# Driver.net
KiCad netlist of a schematic drawn in EAGLE
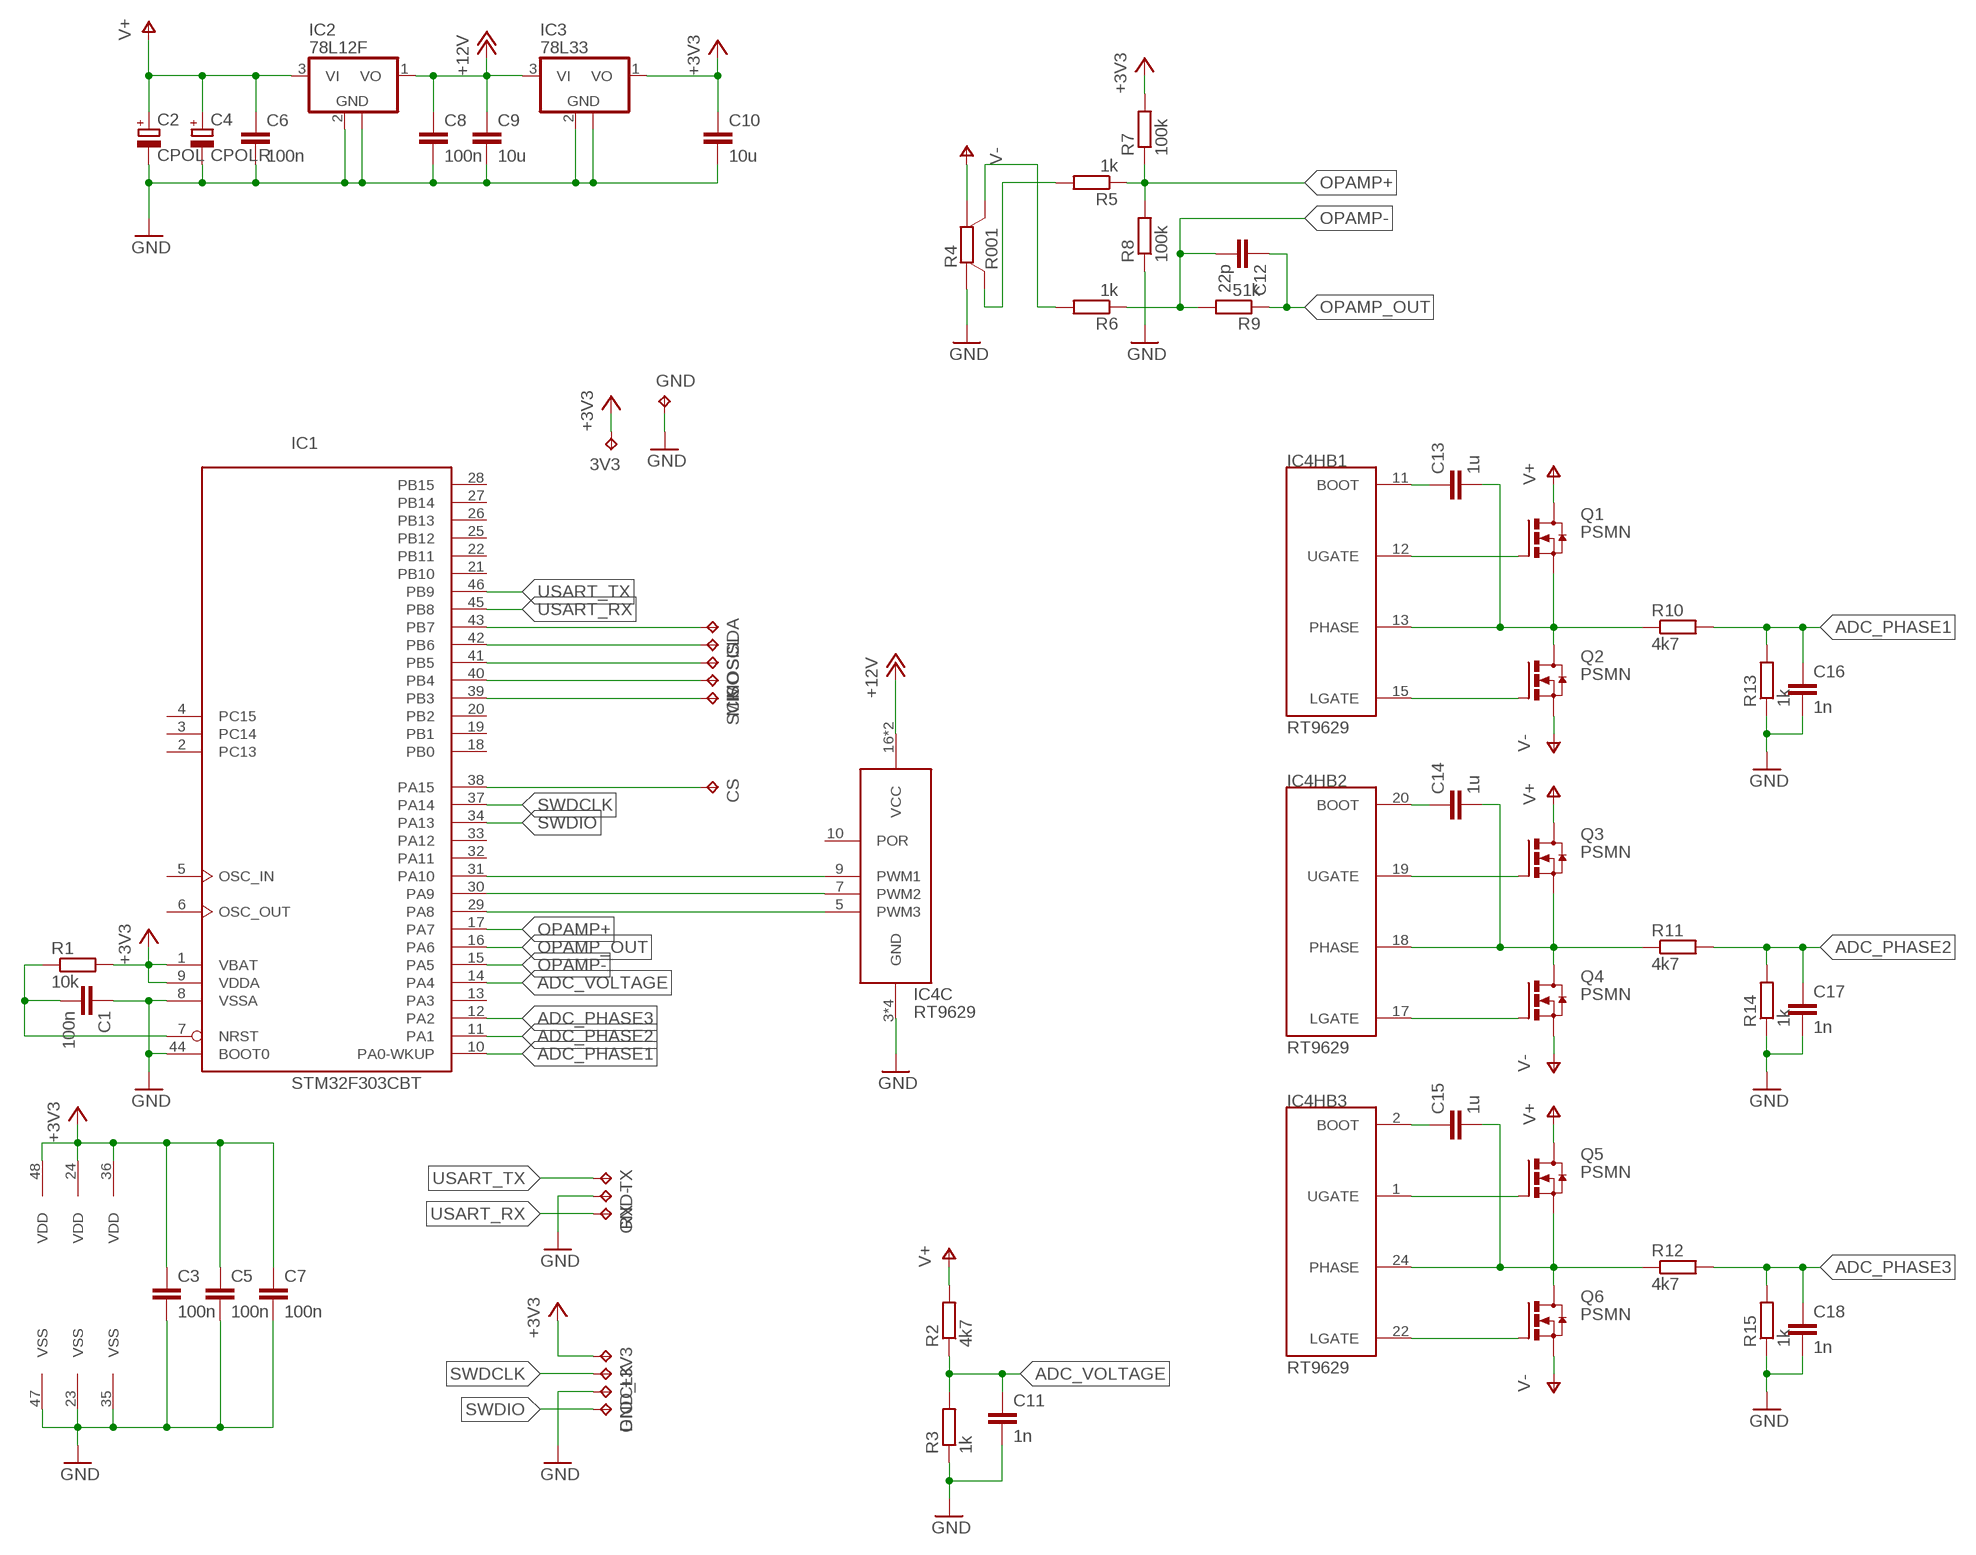
[diagram p0: schematic, sheet 1]

(export (version "E")
  (design (tool "Eeschema 10.0.6"))
  (components
    (comp (ref "+3V3")
      (value "TPTP15R")
      (footprint "eagle-import:TP15R")
      (libsource (lib "eagle-import") (part "TPTP15R"))
    )
    (comp (ref "3V3")
      (value "TPTP10SQ")
      (footprint "eagle-import:TP10SQ")
      (libsource (lib "eagle-import") (part "TPTP10SQ"))
    )
    (comp (ref "C1")
      (value "100n")
      (footprint "eagle-import:C0603K")
      (libsource (lib "eagle-import") (part "C-EUC0603K"))
    )
    (comp (ref "C2")
      (value "CPOL")
      (footprint "eagle-import:SIDEWAYS-5.08")
      (libsource (lib "eagle-import") (part "CPOL"))
    )
    (comp (ref "C3")
      (value "100n")
      (footprint "eagle-import:C0603K")
      (libsource (lib "eagle-import") (part "C-EUC0603K"))
    )
    (comp (ref "C4")
      (value "CPOLR")
      (footprint "eagle-import:SIDEWAYS-5.08R")
      (libsource (lib "eagle-import") (part "CPOLR"))
    )
    (comp (ref "C5")
      (value "100n")
      (footprint "eagle-import:C0603K")
      (libsource (lib "eagle-import") (part "C-EUC0603K"))
    )
    (comp (ref "C6")
      (value "100n")
      (footprint "eagle-import:C0603K")
      (libsource (lib "eagle-import") (part "C-EUC0603K"))
    )
    (comp (ref "C7")
      (value "100n")
      (footprint "eagle-import:C0603K")
      (libsource (lib "eagle-import") (part "C-EUC0603K"))
    )
    (comp (ref "C8")
      (value "100n")
      (footprint "eagle-import:C0603K")
      (libsource (lib "eagle-import") (part "C-EUC0603K"))
    )
    (comp (ref "C9")
      (value "10u")
      (footprint "eagle-import:C1206K")
      (libsource (lib "eagle-import") (part "C-EUC1206K"))
    )
    (comp (ref "C10")
      (value "10u")
      (footprint "eagle-import:C1206K")
      (libsource (lib "eagle-import") (part "C-EUC1206K"))
    )
    (comp (ref "C11")
      (value "1n")
      (footprint "eagle-import:C0603K")
      (libsource (lib "eagle-import") (part "C-EUC0603K"))
    )
    (comp (ref "C12")
      (value "22p")
      (footprint "eagle-import:C0603K")
      (libsource (lib "eagle-import") (part "C-EUC0603K"))
    )
    (comp (ref "C13")
      (value "1u")
      (footprint "eagle-import:C0603K")
      (libsource (lib "eagle-import") (part "C-EUC0603K"))
    )
    (comp (ref "C14")
      (value "1u")
      (footprint "eagle-import:C0603K")
      (libsource (lib "eagle-import") (part "C-EUC0603K"))
    )
    (comp (ref "C15")
      (value "1u")
      (footprint "eagle-import:C0603K")
      (libsource (lib "eagle-import") (part "C-EUC0603K"))
    )
    (comp (ref "C16")
      (value "1n")
      (footprint "eagle-import:C0603K")
      (libsource (lib "eagle-import") (part "C-EUC0603K"))
    )
    (comp (ref "C17")
      (value "1n")
      (footprint "eagle-import:C0603K")
      (libsource (lib "eagle-import") (part "C-EUC0603K"))
    )
    (comp (ref "C18")
      (value "1n")
      (footprint "eagle-import:C0603K")
      (libsource (lib "eagle-import") (part "C-EUC0603K"))
    )
    (comp (ref "CLK")
      (value "TPTP15R")
      (footprint "eagle-import:TP15R")
      (libsource (lib "eagle-import") (part "TPTP15R"))
    )
    (comp (ref "CS")
      (value "TPTP10SQ")
      (footprint "eagle-import:TP10SQ")
      (libsource (lib "eagle-import") (part "TPTP10SQ"))
    )
    (comp (ref "DIO")
      (value "TPTP15R")
      (footprint "eagle-import:TP15R")
      (libsource (lib "eagle-import") (part "TPTP15R"))
    )
    (comp (ref "GND")
      (value "TPTP10SQ")
      (footprint "eagle-import:TP10SQ")
      (libsource (lib "eagle-import") (part "TPTP10SQ"))
    )
    (comp (ref "GND-")
      (value "TPTP15SQ")
      (footprint "eagle-import:TP15SQ")
      (libsource (lib "eagle-import") (part "TPTP15SQ"))
    )
    (comp (ref "GND_")
      (value "TPTP15SQ")
      (footprint "eagle-import:TP15SQ")
      (libsource (lib "eagle-import") (part "TPTP15SQ"))
    )
    (comp (ref "IC1")
      (value "STM32F303CBT")
      (footprint "eagle-import:LQFP48")
      (libsource (lib "eagle-import") (part "STM32F303CTB"))
    )
    (comp (ref "IC2")
      (value "78L12F")
      (footprint "eagle-import:SOT89")
      (libsource (lib "eagle-import") (part "78LF12"))
    )
    (comp (ref "IC3")
      (value "78L33")
      (footprint "eagle-import:SOT89")
      (libsource (lib "eagle-import") (part "78LF12"))
    )
    (comp (ref "IC4")
      (value "RT9629")
      (footprint "eagle-import:WQFN24")
      (libsource (lib "eagle-import") (part "RT9629"))
    )
    (comp (ref "MISO")
      (value "TPTP10SQ")
      (footprint "eagle-import:TP10SQ")
      (libsource (lib "eagle-import") (part "TPTP10SQ"))
    )
    (comp (ref "MOSI")
      (value "TPTP10SQ")
      (footprint "eagle-import:TP10SQ")
      (libsource (lib "eagle-import") (part "TPTP10SQ"))
    )
    (comp (ref "Q1")
      (value "PSMN")
      (footprint "eagle-import:SOT669")
      (libsource (lib "eagle-import") (part "PSMN"))
    )
    (comp (ref "Q2")
      (value "PSMN")
      (footprint "eagle-import:SOT669")
      (libsource (lib "eagle-import") (part "PSMN"))
    )
    (comp (ref "Q3")
      (value "PSMN")
      (footprint "eagle-import:SOT669")
      (libsource (lib "eagle-import") (part "PSMN"))
    )
    (comp (ref "Q4")
      (value "PSMN")
      (footprint "eagle-import:SOT669")
      (libsource (lib "eagle-import") (part "PSMN"))
    )
    (comp (ref "Q5")
      (value "PSMN")
      (footprint "eagle-import:SOT669")
      (libsource (lib "eagle-import") (part "PSMN"))
    )
    (comp (ref "Q6")
      (value "PSMN")
      (footprint "eagle-import:SOT669")
      (libsource (lib "eagle-import") (part "PSMN"))
    )
    (comp (ref "R1")
      (value "10k")
      (footprint "eagle-import:R0603")
      (libsource (lib "eagle-import") (part "R-EU_R0603"))
    )
    (comp (ref "R2")
      (value "4k7")
      (footprint "eagle-import:R0603")
      (libsource (lib "eagle-import") (part "R-EU_R0603"))
    )
    (comp (ref "R3")
      (value "1k")
      (footprint "eagle-import:R0603")
      (libsource (lib "eagle-import") (part "R-EU_R0603"))
    )
    (comp (ref "R4")
      (value "R001")
      (footprint "eagle-import:WSK1216")
      (libsource (lib "eagle-import") (part "VISHAY_WSK1216"))
    )
    (comp (ref "R5")
      (value "1k")
      (footprint "eagle-import:R0603")
      (libsource (lib "eagle-import") (part "R-EU_R0603"))
    )
    (comp (ref "R6")
      (value "1k")
      (footprint "eagle-import:R0603")
      (libsource (lib "eagle-import") (part "R-EU_R0603"))
    )
    (comp (ref "R7")
      (value "100k")
      (footprint "eagle-import:R0603")
      (libsource (lib "eagle-import") (part "R-EU_R0603"))
    )
    (comp (ref "R8")
      (value "100k")
      (footprint "eagle-import:R0603")
      (libsource (lib "eagle-import") (part "R-EU_R0603"))
    )
    (comp (ref "R9")
      (value "51k")
      (footprint "eagle-import:R0603")
      (libsource (lib "eagle-import") (part "R-EU_R0603"))
    )
    (comp (ref "R10")
      (value "4k7")
      (footprint "eagle-import:R0603")
      (libsource (lib "eagle-import") (part "R-EU_R0603"))
    )
    (comp (ref "R11")
      (value "4k7")
      (footprint "eagle-import:R0603")
      (libsource (lib "eagle-import") (part "R-EU_R0603"))
    )
    (comp (ref "R12")
      (value "4k7")
      (footprint "eagle-import:R0603")
      (libsource (lib "eagle-import") (part "R-EU_R0603"))
    )
    (comp (ref "R13")
      (value "1k")
      (footprint "eagle-import:R0603")
      (libsource (lib "eagle-import") (part "R-EU_R0603"))
    )
    (comp (ref "R14")
      (value "1k")
      (footprint "eagle-import:R0603")
      (libsource (lib "eagle-import") (part "R-EU_R0603"))
    )
    (comp (ref "R15")
      (value "1k")
      (footprint "eagle-import:R0603")
      (libsource (lib "eagle-import") (part "R-EU_R0603"))
    )
    (comp (ref "RX")
      (value "TPTP15R")
      (footprint "eagle-import:TP15R")
      (libsource (lib "eagle-import") (part "TPTP15R"))
    )
    (comp (ref "SCK")
      (value "TPTP10SQ")
      (footprint "eagle-import:TP10SQ")
      (libsource (lib "eagle-import") (part "TPTP10SQ"))
    )
    (comp (ref "SCL")
      (value "TPTP10SQ")
      (footprint "eagle-import:TP10SQ")
      (libsource (lib "eagle-import") (part "TPTP10SQ"))
    )
    (comp (ref "SDA")
      (value "TPTP10SQ")
      (footprint "eagle-import:TP10SQ")
      (libsource (lib "eagle-import") (part "TPTP10SQ"))
    )
    (comp (ref "TX")
      (value "TPTP15R")
      (footprint "eagle-import:TP15R")
      (libsource (lib "eagle-import") (part "TPTP15R"))
    )
  )
  (nets
    (net (code "1") (name "+3V3") (class "Default")
      (node (ref "+3V3") (pin "TP") (pinfunction "TP_TP") (pintype "input"))
      (node (ref "3V3") (pin "TP") (pinfunction "TP_TP") (pintype "input"))
      (node (ref "C10") (pin "1") (pinfunction "1_1") (pintype "passive"))
      (node (ref "C3") (pin "1") (pinfunction "1_1") (pintype "passive"))
      (node (ref "C5") (pin "1") (pinfunction "1_1") (pintype "passive"))
      (node (ref "C7") (pin "1") (pinfunction "1_1") (pintype "passive"))
      (node (ref "IC1") (pin "1") (pinfunction "VBAT_1") (pintype "power_in"))
      (node (ref "IC1") (pin "24") (pinfunction "VDD_24") (pintype "power_in"))
      (node (ref "IC1") (pin "36") (pinfunction "VDD_36") (pintype "power_in"))
      (node (ref "IC1") (pin "48") (pinfunction "VDD_48") (pintype "power_in"))
      (node (ref "IC1") (pin "9") (pinfunction "VDDA_9") (pintype "power_in"))
      (node (ref "IC3") (pin "1") (pinfunction "VO_1") (pintype "passive"))
      (node (ref "R1") (pin "2") (pinfunction "2_2") (pintype "passive"))
      (node (ref "R7") (pin "2") (pinfunction "2_2") (pintype "passive"))
    )
    (net (code "2") (name "+12V") (class "Default")
      (node (ref "C8") (pin "1") (pinfunction "1_1") (pintype "passive"))
      (node (ref "C9") (pin "1") (pinfunction "1_1") (pintype "passive"))
      (node (ref "IC2") (pin "1") (pinfunction "VO_1") (pintype "passive"))
      (node (ref "IC3") (pin "3") (pinfunction "VI_3") (pintype "input"))
      (node (ref "IC4") (pin "16") (pinfunction "VCC_16") (pintype "bidirectional"))
      (node (ref "IC4") (pin "21") (pinfunction "VCC_21") (pintype "bidirectional"))
    )
    (net (code "3") (name "ADC_PHASE1") (class "Default")
      (node (ref "C16") (pin "1") (pinfunction "1_1") (pintype "passive"))
      (node (ref "IC1") (pin "10") (pinfunction "PA0-WKUP_10") (pintype "bidirectional"))
      (node (ref "R10") (pin "2") (pinfunction "2_2") (pintype "passive"))
      (node (ref "R13") (pin "2") (pinfunction "2_2") (pintype "passive"))
    )
    (net (code "4") (name "ADC_PHASE2") (class "Default")
      (node (ref "C17") (pin "1") (pinfunction "1_1") (pintype "passive"))
      (node (ref "IC1") (pin "11") (pinfunction "PA1_11") (pintype "bidirectional"))
      (node (ref "R11") (pin "2") (pinfunction "2_2") (pintype "passive"))
      (node (ref "R14") (pin "2") (pinfunction "2_2") (pintype "passive"))
    )
    (net (code "5") (name "ADC_PHASE3") (class "Default")
      (node (ref "C18") (pin "1") (pinfunction "1_1") (pintype "passive"))
      (node (ref "IC1") (pin "12") (pinfunction "PA2_12") (pintype "bidirectional"))
      (node (ref "R12") (pin "2") (pinfunction "2_2") (pintype "passive"))
      (node (ref "R15") (pin "2") (pinfunction "2_2") (pintype "passive"))
    )
    (net (code "6") (name "ADC_VOLTAGE") (class "Default")
      (node (ref "C11") (pin "1") (pinfunction "1_1") (pintype "passive"))
      (node (ref "IC1") (pin "14") (pinfunction "PA4_14") (pintype "bidirectional"))
      (node (ref "R2") (pin "1") (pinfunction "1_1") (pintype "passive"))
      (node (ref "R3") (pin "2") (pinfunction "2_2") (pintype "passive"))
    )
    (net (code "7") (name "GND") (class "Default")
      (node (ref "C1") (pin "1") (pinfunction "1_1") (pintype "passive"))
      (node (ref "C10") (pin "2") (pinfunction "2_2") (pintype "passive"))
      (node (ref "C11") (pin "2") (pinfunction "2_2") (pintype "passive"))
      (node (ref "C16") (pin "2") (pinfunction "2_2") (pintype "passive"))
      (node (ref "C17") (pin "2") (pinfunction "2_2") (pintype "passive"))
      (node (ref "C18") (pin "2") (pinfunction "2_2") (pintype "passive"))
      (node (ref "C2") (pin "-") (pinfunction "-_-") (pintype "passive"))
      (node (ref "C3") (pin "2") (pinfunction "2_2") (pintype "passive"))
      (node (ref "C4") (pin "-") (pinfunction "-_-") (pintype "passive"))
      (node (ref "C5") (pin "2") (pinfunction "2_2") (pintype "passive"))
      (node (ref "C6") (pin "2") (pinfunction "2_2") (pintype "passive"))
      (node (ref "C7") (pin "2") (pinfunction "2_2") (pintype "passive"))
      (node (ref "C8") (pin "2") (pinfunction "2_2") (pintype "passive"))
      (node (ref "C9") (pin "2") (pinfunction "2_2") (pintype "passive"))
      (node (ref "GND") (pin "TP") (pinfunction "TP_TP") (pintype "input"))
      (node (ref "GND-") (pin "TP") (pinfunction "TP_TP") (pintype "input"))
      (node (ref "GND_") (pin "TP") (pinfunction "TP_TP") (pintype "input"))
      (node (ref "IC1") (pin "23") (pinfunction "VSS_23") (pintype "power_in"))
      (node (ref "IC1") (pin "35") (pinfunction "VSS_35") (pintype "power_in"))
      (node (ref "IC1") (pin "44") (pinfunction "BOOT0_44") (pintype "input"))
      (node (ref "IC1") (pin "47") (pinfunction "VSS_47") (pintype "power_in"))
      (node (ref "IC1") (pin "8") (pinfunction "VSSA_8") (pintype "power_in"))
      (node (ref "IC2") (pin "2") (pinfunction "GND_2") (pintype "passive"))
      (node (ref "IC2") (pin "2@1") (pinfunction "GND_2@1") (pintype "passive"))
      (node (ref "IC3") (pin "2") (pinfunction "GND_2") (pintype "passive"))
      (node (ref "IC3") (pin "2@1") (pinfunction "GND_2@1") (pintype "passive"))
      (node (ref "IC4") (pin "14") (pinfunction "GND_14") (pintype "bidirectional"))
      (node (ref "IC4") (pin "23") (pinfunction "GND_23") (pintype "bidirectional"))
      (node (ref "IC4") (pin "3") (pinfunction "GND_3") (pintype "bidirectional"))
      (node (ref "IC4") (pin "E") (pinfunction "GND_E") (pintype "bidirectional"))
      (node (ref "R13") (pin "1") (pinfunction "1_1") (pintype "passive"))
      (node (ref "R14") (pin "1") (pinfunction "1_1") (pintype "passive"))
      (node (ref "R15") (pin "1") (pinfunction "1_1") (pintype "passive"))
      (node (ref "R3") (pin "1") (pinfunction "1_1") (pintype "passive"))
      (node (ref "R4") (pin "B") (pinfunction "B_B") (pintype "passive"))
      (node (ref "R8") (pin "1") (pinfunction "1_1") (pintype "passive"))
    )
    (net (code "8") (name "Net-(IC1A-NRST)") (class "Default")
      (node (ref "C1") (pin "2") (pinfunction "2_2") (pintype "passive"))
      (node (ref "IC1") (pin "7") (pinfunction "NRST_7") (pintype "bidirectional"))
      (node (ref "R1") (pin "1") (pinfunction "1_1") (pintype "passive"))
    )
    (net (code "9") (name "Net-(IC1A-PA8)") (class "Default")
      (node (ref "IC1") (pin "29") (pinfunction "PA8_29") (pintype "bidirectional"))
      (node (ref "IC4") (pin "5") (pinfunction "PWM3_5") (pintype "bidirectional"))
    )
    (net (code "10") (name "Net-(IC1A-PA9)") (class "Default")
      (node (ref "IC1") (pin "30") (pinfunction "PA9_30") (pintype "bidirectional"))
      (node (ref "IC4") (pin "7") (pinfunction "PWM2_7") (pintype "bidirectional"))
    )
    (net (code "11") (name "Net-(IC1A-PA10)") (class "Default")
      (node (ref "IC1") (pin "31") (pinfunction "PA10_31") (pintype "bidirectional"))
      (node (ref "IC4") (pin "9") (pinfunction "PWM1_9") (pintype "bidirectional"))
    )
    (net (code "12") (name "Net-(IC1A-PA15)") (class "Default")
      (node (ref "CS") (pin "TP") (pinfunction "TP_TP") (pintype "input"))
      (node (ref "IC1") (pin "38") (pinfunction "PA15_38") (pintype "bidirectional"))
    )
    (net (code "13") (name "Net-(IC1A-PB3)") (class "Default")
      (node (ref "IC1") (pin "39") (pinfunction "PB3_39") (pintype "bidirectional"))
      (node (ref "SCK") (pin "TP") (pinfunction "TP_TP") (pintype "input"))
    )
    (net (code "14") (name "Net-(IC1A-PB4)") (class "Default")
      (node (ref "IC1") (pin "40") (pinfunction "PB4_40") (pintype "bidirectional"))
      (node (ref "MISO") (pin "TP") (pinfunction "TP_TP") (pintype "input"))
    )
    (net (code "15") (name "Net-(IC1A-PB5)") (class "Default")
      (node (ref "IC1") (pin "41") (pinfunction "PB5_41") (pintype "bidirectional"))
      (node (ref "MOSI") (pin "TP") (pinfunction "TP_TP") (pintype "input"))
    )
    (net (code "16") (name "Net-(IC1A-PB6)") (class "Default")
      (node (ref "IC1") (pin "42") (pinfunction "PB6_42") (pintype "bidirectional"))
      (node (ref "SCL") (pin "TP") (pinfunction "TP_TP") (pintype "input"))
    )
    (net (code "17") (name "Net-(IC1A-PB7)") (class "Default")
      (node (ref "IC1") (pin "43") (pinfunction "PB7_43") (pintype "bidirectional"))
      (node (ref "SDA") (pin "TP") (pinfunction "TP_TP") (pintype "input"))
    )
    (net (code "18") (name "Net-(IC4B-BOOT)") (class "Default")
      (node (ref "C13") (pin "1") (pinfunction "1_1") (pintype "passive"))
      (node (ref "IC4") (pin "11") (pinfunction "BOOT_11") (pintype "bidirectional"))
    )
    (net (code "19") (name "Net-(IC4B-LGATE)") (class "Default")
      (node (ref "IC4") (pin "15") (pinfunction "LGATE_15") (pintype "bidirectional"))
      (node (ref "Q2") (pin "4") (pinfunction "G_4") (pintype "passive"))
    )
    (net (code "20") (name "Net-(IC4B-PHASE)") (class "Default")
      (node (ref "C13") (pin "2") (pinfunction "2_2") (pintype "passive"))
      (node (ref "IC4") (pin "13") (pinfunction "PHASE_13") (pintype "bidirectional"))
      (node (ref "Q1") (pin "1") (pinfunction "S_1") (pintype "passive"))
      (node (ref "Q1") (pin "2") (pinfunction "S_2") (pintype "passive"))
      (node (ref "Q1") (pin "3") (pinfunction "S_3") (pintype "passive"))
      (node (ref "Q2") (pin "MB") (pinfunction "D_MB") (pintype "passive"))
      (node (ref "R10") (pin "1") (pinfunction "1_1") (pintype "passive"))
    )
    (net (code "21") (name "Net-(IC4B-UGATE)") (class "Default")
      (node (ref "IC4") (pin "12") (pinfunction "UGATE_12") (pintype "bidirectional"))
      (node (ref "Q1") (pin "4") (pinfunction "G_4") (pintype "passive"))
    )
    (net (code "22") (name "Net-(IC4C-BOOT)") (class "Default")
      (node (ref "C14") (pin "1") (pinfunction "1_1") (pintype "passive"))
      (node (ref "IC4") (pin "20") (pinfunction "BOOT_20") (pintype "bidirectional"))
    )
    (net (code "23") (name "Net-(IC4C-LGATE)") (class "Default")
      (node (ref "IC4") (pin "17") (pinfunction "LGATE_17") (pintype "bidirectional"))
      (node (ref "Q4") (pin "4") (pinfunction "G_4") (pintype "passive"))
    )
    (net (code "24") (name "Net-(IC4C-PHASE)") (class "Default")
      (node (ref "C14") (pin "2") (pinfunction "2_2") (pintype "passive"))
      (node (ref "IC4") (pin "18") (pinfunction "PHASE_18") (pintype "bidirectional"))
      (node (ref "Q3") (pin "1") (pinfunction "S_1") (pintype "passive"))
      (node (ref "Q3") (pin "2") (pinfunction "S_2") (pintype "passive"))
      (node (ref "Q3") (pin "3") (pinfunction "S_3") (pintype "passive"))
      (node (ref "Q4") (pin "MB") (pinfunction "D_MB") (pintype "passive"))
      (node (ref "R11") (pin "1") (pinfunction "1_1") (pintype "passive"))
    )
    (net (code "25") (name "Net-(IC4C-UGATE)") (class "Default")
      (node (ref "IC4") (pin "19") (pinfunction "UGATE_19") (pintype "bidirectional"))
      (node (ref "Q3") (pin "4") (pinfunction "G_4") (pintype "passive"))
    )
    (net (code "26") (name "Net-(IC4D-BOOT)") (class "Default")
      (node (ref "C15") (pin "1") (pinfunction "1_1") (pintype "passive"))
      (node (ref "IC4") (pin "2") (pinfunction "BOOT_2") (pintype "bidirectional"))
    )
    (net (code "27") (name "Net-(IC4D-LGATE)") (class "Default")
      (node (ref "IC4") (pin "22") (pinfunction "LGATE_22") (pintype "bidirectional"))
      (node (ref "Q6") (pin "4") (pinfunction "G_4") (pintype "passive"))
    )
    (net (code "28") (name "Net-(IC4D-PHASE)") (class "Default")
      (node (ref "C15") (pin "2") (pinfunction "2_2") (pintype "passive"))
      (node (ref "IC4") (pin "24") (pinfunction "PHASE_24") (pintype "bidirectional"))
      (node (ref "Q5") (pin "1") (pinfunction "S_1") (pintype "passive"))
      (node (ref "Q5") (pin "2") (pinfunction "S_2") (pintype "passive"))
      (node (ref "Q5") (pin "3") (pinfunction "S_3") (pintype "passive"))
      (node (ref "Q6") (pin "MB") (pinfunction "D_MB") (pintype "passive"))
      (node (ref "R12") (pin "1") (pinfunction "1_1") (pintype "passive"))
    )
    (net (code "29") (name "Net-(IC4D-UGATE)") (class "Default")
      (node (ref "IC4") (pin "1") (pinfunction "UGATE_1") (pintype "bidirectional"))
      (node (ref "Q5") (pin "4") (pinfunction "G_4") (pintype "passive"))
    )
    (net (code "30") (name "Net-(R4-PadSA)") (class "Default")
      (node (ref "R4") (pin "SA") (pinfunction "SA_SA") (pintype "passive"))
      (node (ref "R6") (pin "2") (pinfunction "2_2") (pintype "passive"))
    )
    (net (code "31") (name "Net-(R4-PadSB)") (class "Default")
      (node (ref "R4") (pin "SB") (pinfunction "SB_SB") (pintype "passive"))
      (node (ref "R5") (pin "2") (pinfunction "2_2") (pintype "passive"))
    )
    (net (code "32") (name "OPAMP+") (class "Default")
      (node (ref "IC1") (pin "17") (pinfunction "PA7_17") (pintype "bidirectional"))
      (node (ref "R5") (pin "1") (pinfunction "1_1") (pintype "passive"))
      (node (ref "R7") (pin "1") (pinfunction "1_1") (pintype "passive"))
      (node (ref "R8") (pin "2") (pinfunction "2_2") (pintype "passive"))
    )
    (net (code "33") (name "OPAMP-") (class "Default")
      (node (ref "C12") (pin "2") (pinfunction "2_2") (pintype "passive"))
      (node (ref "IC1") (pin "15") (pinfunction "PA5_15") (pintype "bidirectional"))
      (node (ref "R6") (pin "1") (pinfunction "1_1") (pintype "passive"))
      (node (ref "R9") (pin "2") (pinfunction "2_2") (pintype "passive"))
    )
    (net (code "34") (name "OPAMP_OUT") (class "Default")
      (node (ref "C12") (pin "1") (pinfunction "1_1") (pintype "passive"))
      (node (ref "IC1") (pin "16") (pinfunction "PA6_16") (pintype "bidirectional"))
      (node (ref "R9") (pin "1") (pinfunction "1_1") (pintype "passive"))
    )
    (net (code "35") (name "SWDCLK") (class "Default")
      (node (ref "CLK") (pin "TP") (pinfunction "TP_TP") (pintype "input"))
      (node (ref "IC1") (pin "37") (pinfunction "PA14_37") (pintype "bidirectional"))
    )
    (net (code "36") (name "SWDIO") (class "Default")
      (node (ref "DIO") (pin "TP") (pinfunction "TP_TP") (pintype "input"))
      (node (ref "IC1") (pin "34") (pinfunction "PA13_34") (pintype "bidirectional"))
    )
    (net (code "37") (name "USART_RX") (class "Default")
      (node (ref "IC1") (pin "45") (pinfunction "PB8_45") (pintype "bidirectional"))
      (node (ref "RX") (pin "TP") (pinfunction "TP_TP") (pintype "input"))
    )
    (net (code "38") (name "USART_TX") (class "Default")
      (node (ref "IC1") (pin "46") (pinfunction "PB9_46") (pintype "bidirectional"))
      (node (ref "TX") (pin "TP") (pinfunction "TP_TP") (pintype "input"))
    )
    (net (code "39") (name "V+") (class "Default")
      (node (ref "C2") (pin "+") (pinfunction "+_+") (pintype "passive"))
      (node (ref "C4") (pin "+") (pinfunction "+_+") (pintype "passive"))
      (node (ref "C6") (pin "1") (pinfunction "1_1") (pintype "passive"))
      (node (ref "IC2") (pin "3") (pinfunction "VI_3") (pintype "input"))
      (node (ref "Q1") (pin "MB") (pinfunction "D_MB") (pintype "passive"))
      (node (ref "Q3") (pin "MB") (pinfunction "D_MB") (pintype "passive"))
      (node (ref "Q5") (pin "MB") (pinfunction "D_MB") (pintype "passive"))
      (node (ref "R2") (pin "2") (pinfunction "2_2") (pintype "passive"))
    )
    (net (code "40") (name "V-") (class "Default")
      (node (ref "Q2") (pin "1") (pinfunction "S_1") (pintype "passive"))
      (node (ref "Q2") (pin "2") (pinfunction "S_2") (pintype "passive"))
      (node (ref "Q2") (pin "3") (pinfunction "S_3") (pintype "passive"))
      (node (ref "Q4") (pin "1") (pinfunction "S_1") (pintype "passive"))
      (node (ref "Q4") (pin "2") (pinfunction "S_2") (pintype "passive"))
      (node (ref "Q4") (pin "3") (pinfunction "S_3") (pintype "passive"))
      (node (ref "Q6") (pin "1") (pinfunction "S_1") (pintype "passive"))
      (node (ref "Q6") (pin "2") (pinfunction "S_2") (pintype "passive"))
      (node (ref "Q6") (pin "3") (pinfunction "S_3") (pintype "passive"))
      (node (ref "R4") (pin "A") (pinfunction "A_A") (pintype "passive"))
    )
    (net (code "41") (name "unconnected-(IC1A-OSC_IN-Pad5)") (class "Default")
      (node (ref "IC1") (pin "5") (pinfunction "OSC_IN_5") (pintype "bidirectional"))
    )
    (net (code "42") (name "unconnected-(IC1A-OSC_OUT-Pad6)") (class "Default")
      (node (ref "IC1") (pin "6") (pinfunction "OSC_OUT_6") (pintype "bidirectional"))
    )
    (net (code "43") (name "unconnected-(IC1A-PA3-Pad13)") (class "Default")
      (node (ref "IC1") (pin "13") (pinfunction "PA3_13") (pintype "bidirectional"))
    )
    (net (code "44") (name "unconnected-(IC1A-PA11-Pad32)") (class "Default")
      (node (ref "IC1") (pin "32") (pinfunction "PA11_32") (pintype "bidirectional"))
    )
    (net (code "45") (name "unconnected-(IC1A-PA12-Pad33)") (class "Default")
      (node (ref "IC1") (pin "33") (pinfunction "PA12_33") (pintype "bidirectional"))
    )
    (net (code "46") (name "unconnected-(IC1A-PB0-Pad18)") (class "Default")
      (node (ref "IC1") (pin "18") (pinfunction "PB0_18") (pintype "bidirectional"))
    )
    (net (code "47") (name "unconnected-(IC1A-PB1-Pad19)") (class "Default")
      (node (ref "IC1") (pin "19") (pinfunction "PB1_19") (pintype "bidirectional"))
    )
    (net (code "48") (name "unconnected-(IC1A-PB2-Pad20)") (class "Default")
      (node (ref "IC1") (pin "20") (pinfunction "PB2_20") (pintype "bidirectional"))
    )
    (net (code "49") (name "unconnected-(IC1A-PB10-Pad21)") (class "Default")
      (node (ref "IC1") (pin "21") (pinfunction "PB10_21") (pintype "bidirectional"))
    )
    (net (code "50") (name "unconnected-(IC1A-PB11-Pad22)") (class "Default")
      (node (ref "IC1") (pin "22") (pinfunction "PB11_22") (pintype "bidirectional"))
    )
    (net (code "51") (name "unconnected-(IC1A-PB12-Pad25)") (class "Default")
      (node (ref "IC1") (pin "25") (pinfunction "PB12_25") (pintype "bidirectional"))
    )
    (net (code "52") (name "unconnected-(IC1A-PB13-Pad26)") (class "Default")
      (node (ref "IC1") (pin "26") (pinfunction "PB13_26") (pintype "bidirectional"))
    )
    (net (code "53") (name "unconnected-(IC1A-PB14-Pad27)") (class "Default")
      (node (ref "IC1") (pin "27") (pinfunction "PB14_27") (pintype "bidirectional"))
    )
    (net (code "54") (name "unconnected-(IC1A-PB15-Pad28)") (class "Default")
      (node (ref "IC1") (pin "28") (pinfunction "PB15_28") (pintype "bidirectional"))
    )
    (net (code "55") (name "unconnected-(IC1A-PC13-Pad2)") (class "Default")
      (node (ref "IC1") (pin "2") (pinfunction "PC13_2") (pintype "bidirectional"))
    )
    (net (code "56") (name "unconnected-(IC1A-PC14-Pad3)") (class "Default")
      (node (ref "IC1") (pin "3") (pinfunction "PC14_3") (pintype "bidirectional"))
    )
    (net (code "57") (name "unconnected-(IC1A-PC15-Pad4)") (class "Default")
      (node (ref "IC1") (pin "4") (pinfunction "PC15_4") (pintype "bidirectional"))
    )
    (net (code "58") (name "unconnected-(IC4A-POR-Pad10)") (class "Default")
      (node (ref "IC4") (pin "10") (pinfunction "POR_10") (pintype "bidirectional"))
    )
  )
)
